# RCMX_Rev_00.net
KiCad netlist of a schematic drawn in EAGLE
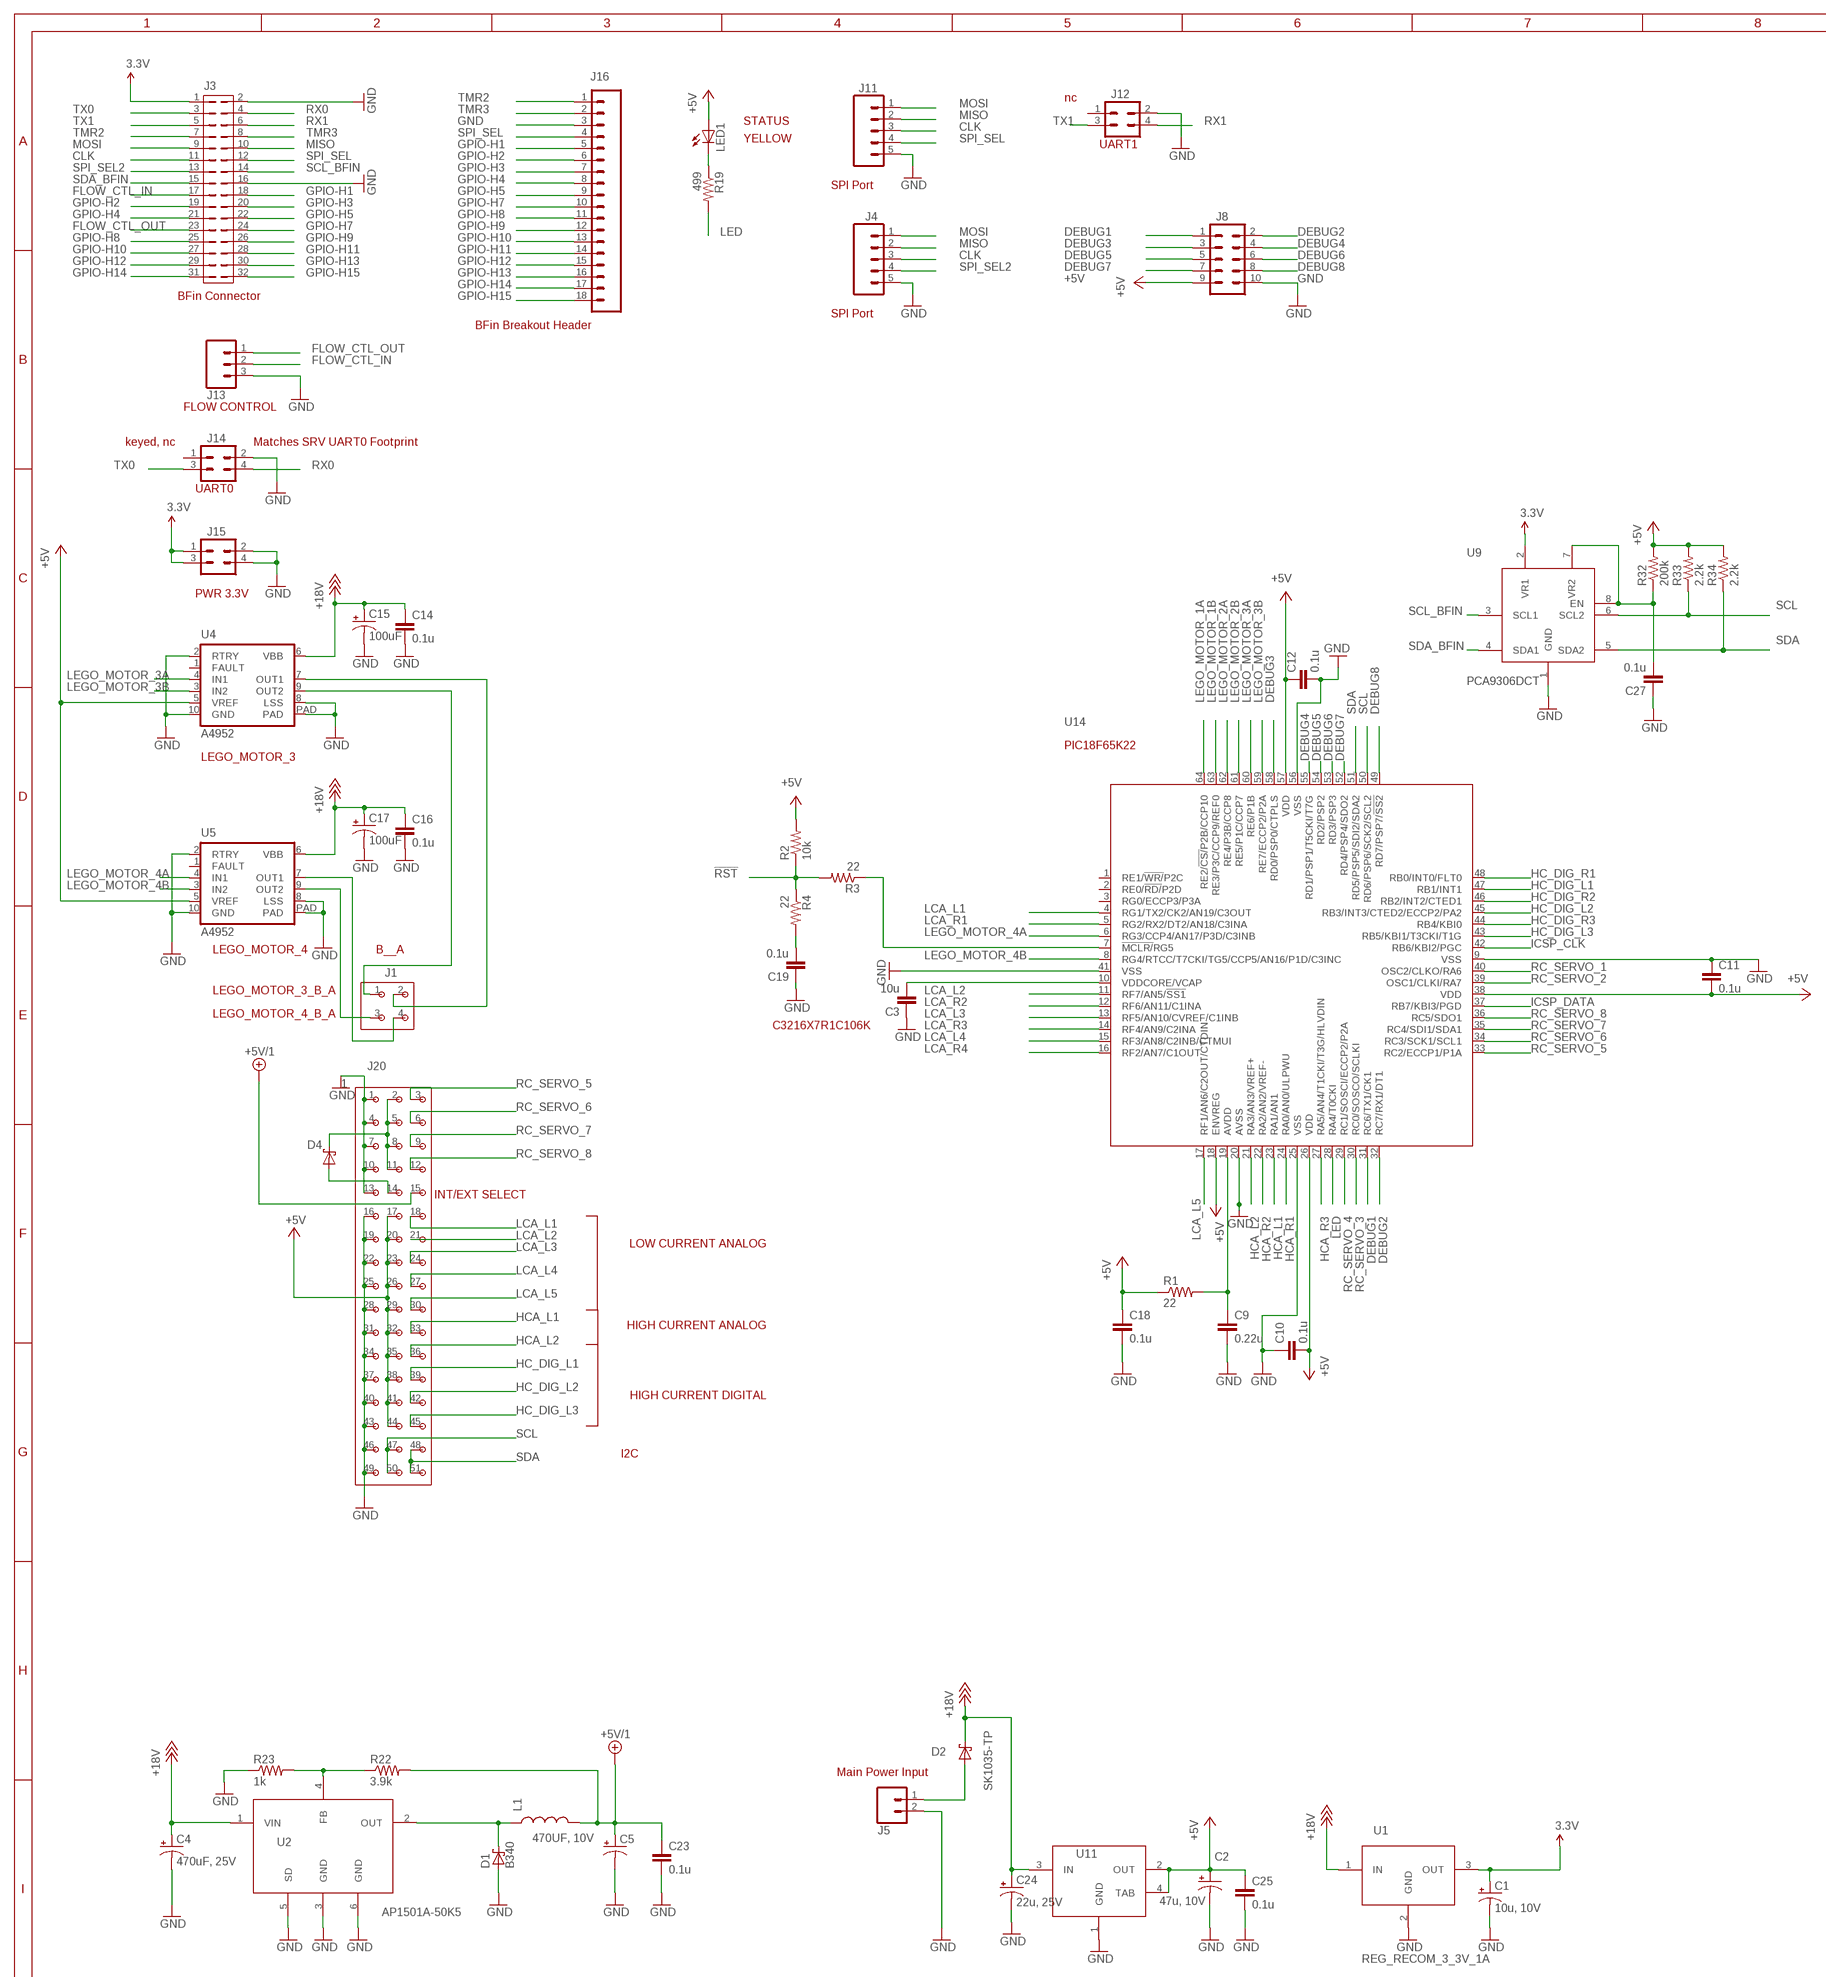
[diagram p0: schematic, sheet 1, part 1 of 2]
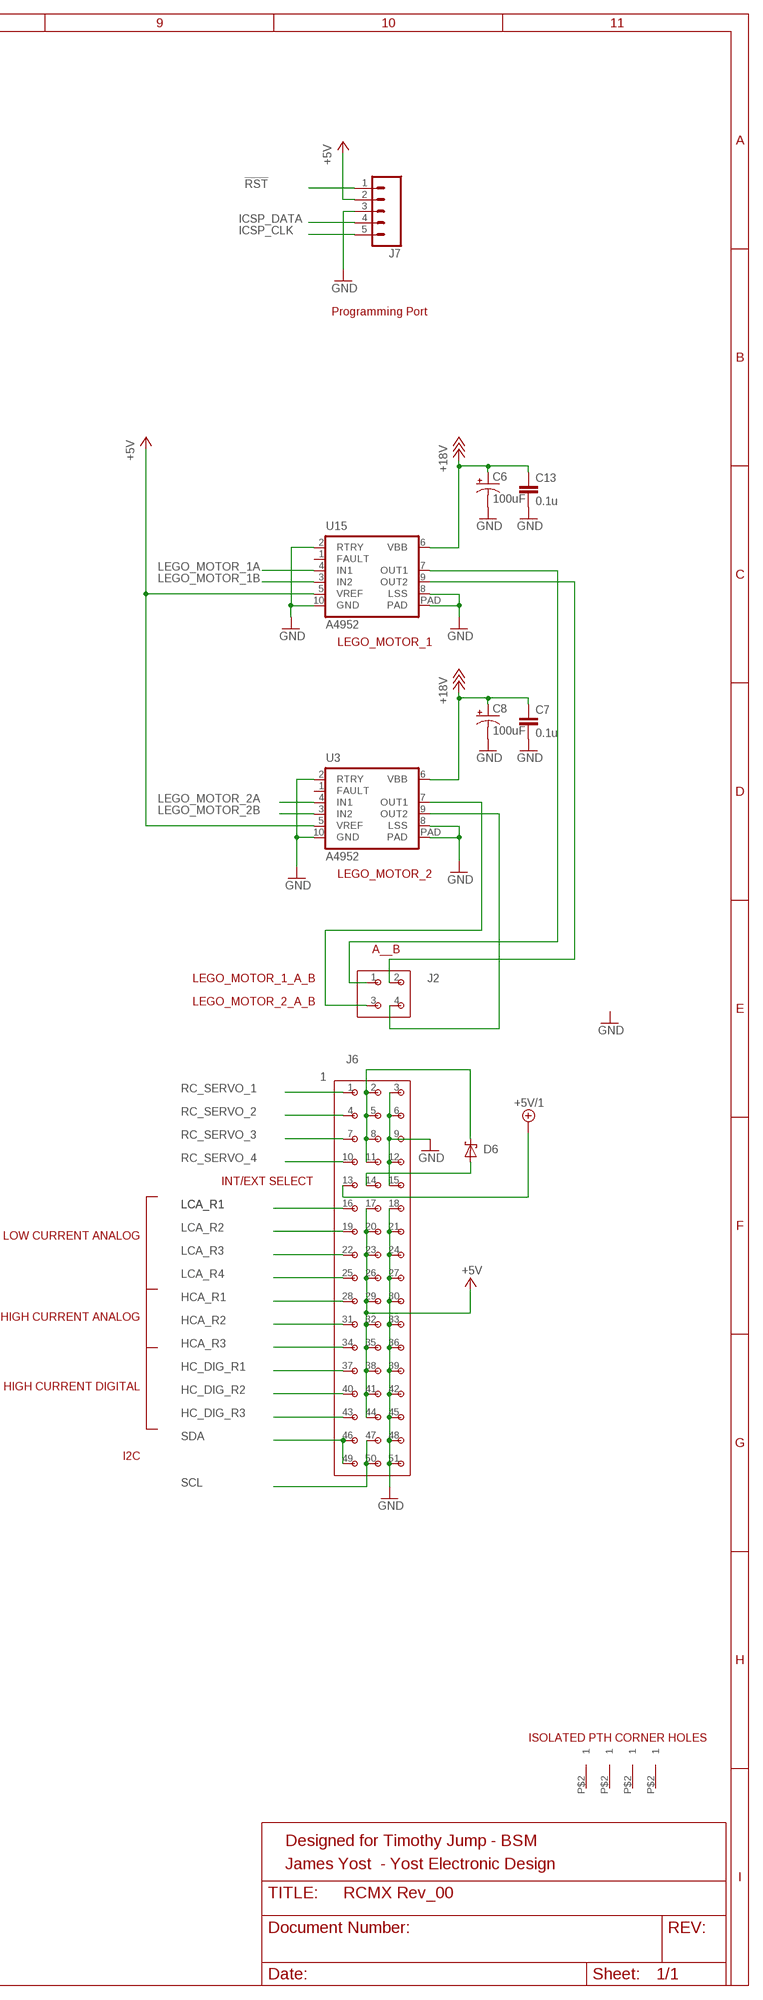
[diagram p1: schematic, sheet 1, part 2 of 2]

(export (version "E")
  (design (tool "Eeschema 10.0.6"))
  (components
    (comp (ref "C1")
      (value "10u, 10V")
      (footprint "eagle-import:EIA3216")
      (libsource (lib "eagle-import") (part "CAP_POL1206"))
    )
    (comp (ref "C2")
      (value "47u, 10V")
      (footprint "eagle-import:CAP1210_POL")
      (libsource (lib "eagle-import") (part "CAP_1210_POL"))
    )
    (comp (ref "C3")
      (value "10u")
      (footprint "eagle-import:1206")
      (libsource (lib "eagle-import") (part "CAP1206"))
    )
    (comp (ref "C4")
      (value "470uF, 25V")
      (footprint "eagle-import:PANASONIC_G")
      (libsource (lib "eagle-import") (part "CAP_POLG"))
    )
    (comp (ref "C5")
      (value "470UF, 10V")
      (footprint "eagle-import:PANASONIC_F")
      (libsource (lib "eagle-import") (part "CAP_ELT_PANASONIC_470UF"))
    )
    (comp (ref "C6")
      (value "100uF")
      (footprint "eagle-import:PANASONIC_D")
      (libsource (lib "eagle-import") (part "CAP_POLD"))
    )
    (comp (ref "C7")
      (value "0.1u")
      (footprint "eagle-import:0805")
      (libsource (lib "eagle-import") (part "CAP0805"))
    )
    (comp (ref "C8")
      (value "100uF")
      (footprint "eagle-import:PANASONIC_D")
      (libsource (lib "eagle-import") (part "CAP_POLD"))
    )
    (comp (ref "C9")
      (value "0.22u")
      (footprint "eagle-import:0805")
      (libsource (lib "eagle-import") (part "CAP0805"))
    )
    (comp (ref "C10")
      (value "0.1u")
      (footprint "eagle-import:0805")
      (libsource (lib "eagle-import") (part "CAP0805"))
    )
    (comp (ref "C11")
      (value "0.1u")
      (footprint "eagle-import:0805")
      (libsource (lib "eagle-import") (part "CAP0805"))
    )
    (comp (ref "C12")
      (value "0.1u")
      (footprint "eagle-import:0805")
      (libsource (lib "eagle-import") (part "CAP0805"))
    )
    (comp (ref "C13")
      (value "0.1u")
      (footprint "eagle-import:0805")
      (libsource (lib "eagle-import") (part "CAP0805"))
    )
    (comp (ref "C14")
      (value "0.1u")
      (footprint "eagle-import:0805")
      (libsource (lib "eagle-import") (part "CAP0805"))
    )
    (comp (ref "C15")
      (value "100uF")
      (footprint "eagle-import:PANASONIC_D")
      (libsource (lib "eagle-import") (part "CAP_POLD"))
    )
    (comp (ref "C16")
      (value "0.1u")
      (footprint "eagle-import:0805")
      (libsource (lib "eagle-import") (part "CAP0805"))
    )
    (comp (ref "C17")
      (value "100uF")
      (footprint "eagle-import:PANASONIC_D")
      (libsource (lib "eagle-import") (part "CAP_POLD"))
    )
    (comp (ref "C18")
      (value "0.1u")
      (footprint "eagle-import:0805")
      (libsource (lib "eagle-import") (part "CAP0805"))
    )
    (comp (ref "C19")
      (value "0.1u")
      (footprint "eagle-import:0805")
      (libsource (lib "eagle-import") (part "CAP0805"))
    )
    (comp (ref "C23")
      (value "0.1u")
      (footprint "eagle-import:0805")
      (libsource (lib "eagle-import") (part "CAP0805"))
    )
    (comp (ref "C24")
      (value "22u, 25V")
      (footprint "eagle-import:CAP1210_POL")
      (libsource (lib "eagle-import") (part "CAP_1210_POL"))
    )
    (comp (ref "C25")
      (value "0.1u")
      (footprint "eagle-import:0805")
      (libsource (lib "eagle-import") (part "CAP0805"))
    )
    (comp (ref "C27")
      (value "0.1u")
      (footprint "eagle-import:0805")
      (libsource (lib "eagle-import") (part "CAP0805"))
    )
    (comp (ref "D1")
      (value "B340")
      (footprint "eagle-import:SMA_DO214AC")
      (libsource (lib "eagle-import") (part "B340"))
    )
    (comp (ref "D2")
      (value "SK1035-TP")
      (footprint "eagle-import:DO214AB")
      (libsource (lib "eagle-import") (part "SK1035-TP"))
    )
    (comp (ref "D4")
      (value "SK1035-TP")
      (footprint "eagle-import:DO214AB")
      (libsource (lib "eagle-import") (part "SK1035-TP"))
    )
    (comp (ref "D6")
      (value "SK1035-TP")
      (footprint "eagle-import:DO214AB")
      (libsource (lib "eagle-import") (part "SK1035-TP"))
    )
    (comp (ref "J1")
      (value "CON_2X2_0_100")
      (footprint "eagle-import:CON_2X2_0_100")
      (libsource (lib "eagle-import") (part "CON_2X2_0_100"))
    )
    (comp (ref "J2")
      (value "CON_2X2_0_100")
      (footprint "eagle-import:CON_2X2_0_100")
      (libsource (lib "eagle-import") (part "CON_2X2_0_100"))
    )
    (comp (ref "J3")
      (value "CON_2X16_0_100")
      (footprint "eagle-import:CON_2X16_0_100")
      (libsource (lib "eagle-import") (part "CON_2X16_0_100"))
    )
    (comp (ref "J4")
      (value "M05PTH")
      (footprint "eagle-import:1X05")
      (libsource (lib "eagle-import") (part "M05PTH"))
    )
    (comp (ref "J5")
      (value "M02NG")
      (footprint "eagle-import:1X02")
      (libsource (lib "eagle-import") (part "M02NG"))
    )
    (comp (ref "J6")
      (value "CON_3X17_0_100")
      (footprint "eagle-import:CON_3X17_0_100")
      (libsource (lib "eagle-import") (part "CON_3X17_0_100"))
    )
    (comp (ref "J7")
      (value "M05PTH")
      (footprint "eagle-import:1X05")
      (libsource (lib "eagle-import") (part "SparkFun-Connectors_M05PTH"))
    )
    (comp (ref "J8")
      (value "M05X2PTH")
      (footprint "eagle-import:AVR_ICSP")
      (libsource (lib "eagle-import") (part "M05X2PTH"))
    )
    (comp (ref "J11")
      (value "M05PTH")
      (footprint "eagle-import:1X05")
      (libsource (lib "eagle-import") (part "M05PTH"))
    )
    (comp (ref "J12")
      (value "CON2X2")
      (footprint "eagle-import:CON2X2")
      (libsource (lib "eagle-import") (part "CON2X2"))
    )
    (comp (ref "J13")
      (value "M03PTH")
      (footprint "eagle-import:1X03")
      (libsource (lib "eagle-import") (part "M03PTH"))
    )
    (comp (ref "J14")
      (value "CON2X2")
      (footprint "eagle-import:CON2X2")
      (libsource (lib "eagle-import") (part "CON2X2"))
    )
    (comp (ref "J15")
      (value "CON2X2")
      (footprint "eagle-import:CON2X2")
      (libsource (lib "eagle-import") (part "CON2X2"))
    )
    (comp (ref "J16")
      (value "CON1X18")
      (footprint "eagle-import:CON1X18")
      (libsource (lib "eagle-import") (part "CON1X18"))
    )
    (comp (ref "J20")
      (value "CON_3X17_0_100")
      (footprint "eagle-import:CON_3X17_0_100")
      (libsource (lib "eagle-import") (part "CON_3X17_0_100"))
    )
    (comp (ref "L1")
      (value "IND_47UH_COILTRONICS_2_95A")
      (footprint "eagle-import:IND_PADS_SMT")
      (libsource (lib "eagle-import") (part "IND_47UH_COILTRONICS_2_95A"))
    )
    (comp (ref "LED1")
      (value "LEDCHIP-LED0805")
      (footprint "eagle-import:CHIP-LED0805")
      (libsource (lib "eagle-import") (part "LEDCHIP-LED0805"))
    )
    (comp (ref "R1")
      (value "22")
      (footprint "eagle-import:0805")
      (libsource (lib "eagle-import") (part "RESISTOR"))
    )
    (comp (ref "R2")
      (value "10k")
      (footprint "eagle-import:0805")
      (libsource (lib "eagle-import") (part "RESISTOR"))
    )
    (comp (ref "R3")
      (value "22")
      (footprint "eagle-import:0805")
      (libsource (lib "eagle-import") (part "RESISTOR"))
    )
    (comp (ref "R4")
      (value "22")
      (footprint "eagle-import:0805")
      (libsource (lib "eagle-import") (part "RESISTOR"))
    )
    (comp (ref "R19")
      (value "499")
      (footprint "eagle-import:0805")
      (libsource (lib "eagle-import") (part "RESISTOR"))
    )
    (comp (ref "R22")
      (value "3.9k")
      (footprint "eagle-import:0805")
      (libsource (lib "eagle-import") (part "RESISTOR"))
    )
    (comp (ref "R23")
      (value "1k")
      (footprint "eagle-import:0805")
      (libsource (lib "eagle-import") (part "RESISTOR"))
    )
    (comp (ref "R32")
      (value "200k")
      (footprint "eagle-import:0805")
      (libsource (lib "eagle-import") (part "RESISTOR"))
    )
    (comp (ref "R33")
      (value "2.2k")
      (footprint "eagle-import:0805")
      (libsource (lib "eagle-import") (part "RESISTOR"))
    )
    (comp (ref "R34")
      (value "2.2k")
      (footprint "eagle-import:0805")
      (libsource (lib "eagle-import") (part "RESISTOR"))
    )
    (comp (ref "U$1")
      (value "GNDPAD")
      (footprint "eagle-import:GNDPAD")
      (libsource (lib "eagle-import") (part "GNDPAD"))
    )
    (comp (ref "U$2")
      (value "GNDPAD")
      (footprint "eagle-import:GNDPAD")
      (libsource (lib "eagle-import") (part "GNDPAD"))
    )
    (comp (ref "U$7")
      (value "GNDPAD")
      (footprint "eagle-import:GNDPAD")
      (libsource (lib "eagle-import") (part "GNDPAD"))
    )
    (comp (ref "U$8")
      (value "GNDPAD")
      (footprint "eagle-import:GNDPAD")
      (libsource (lib "eagle-import") (part "GNDPAD"))
    )
    (comp (ref "U1")
      (value "REG_RECOM_3_3V_1A")
      (footprint "eagle-import:REG_RECOM_3_3V_1A")
      (libsource (lib "eagle-import") (part "REG_RECOM_3_3V_1A"))
    )
    (comp (ref "U2")
      (value "AP1501A-50K5")
      (footprint "eagle-import:TO263-5")
      (libsource (lib "eagle-import") (part "AP1501A-50K5"))
    )
    (comp (ref "U3")
      (value "A4952")
      (footprint "eagle-import:MSOP10_W_THERMAL_PAD")
      (libsource (lib "eagle-import") (part "A4952"))
    )
    (comp (ref "U4")
      (value "A4952")
      (footprint "eagle-import:MSOP10_W_THERMAL_PAD")
      (libsource (lib "eagle-import") (part "A4952"))
    )
    (comp (ref "U5")
      (value "A4952")
      (footprint "eagle-import:MSOP10_W_THERMAL_PAD")
      (libsource (lib "eagle-import") (part "A4952"))
    )
    (comp (ref "U9")
      (value "PCA9306DCT")
      (footprint "eagle-import:TEST08")
      (libsource (lib "eagle-import") (part "PCA9306DCT"))
    )
    (comp (ref "U11")
      (value "TLV1117-5")
      (footprint "eagle-import:SOT223")
      (libsource (lib "eagle-import") (part "TLV1117-5"))
    )
    (comp (ref "U14")
      (value "MICRO_C_PIC18F65K22")
      (footprint "eagle-import:64PIN_TQFP_10X10X1MM")
      (libsource (lib "eagle-import") (part "MICRO_C_PIC18F65K22"))
    )
    (comp (ref "U15")
      (value "A4952")
      (footprint "eagle-import:MSOP10_W_THERMAL_PAD")
      (libsource (lib "eagle-import") (part "A4952"))
    )
  )
  (nets
    (net (code "1") (name "+5V") (class "Default")
      (node (ref "C10") (pin "2") (pinfunction "2_2") (pintype "passive"))
      (node (ref "C11") (pin "2") (pinfunction "2_2") (pintype "passive"))
      (node (ref "C12") (pin "1") (pinfunction "1_1") (pintype "passive"))
      (node (ref "C18") (pin "1") (pinfunction "1_1") (pintype "passive"))
      (node (ref "C2") (pin "1") (pinfunction "+_1") (pintype "passive"))
      (node (ref "C25") (pin "1") (pinfunction "1_1") (pintype "passive"))
      (node (ref "J20") (pin "17") (pinfunction "17_17") (pintype "passive"))
      (node (ref "J20") (pin "20") (pinfunction "20_20") (pintype "passive"))
      (node (ref "J20") (pin "23") (pinfunction "23_23") (pintype "passive"))
      (node (ref "J20") (pin "26") (pinfunction "26_26") (pintype "passive"))
      (node (ref "J20") (pin "29") (pinfunction "29_29") (pintype "passive"))
      (node (ref "J20") (pin "32") (pinfunction "32_32") (pintype "passive"))
      (node (ref "J20") (pin "35") (pinfunction "35_35") (pintype "passive"))
      (node (ref "J20") (pin "38") (pinfunction "38_38") (pintype "passive"))
      (node (ref "J20") (pin "41") (pinfunction "41_41") (pintype "passive"))
      (node (ref "J20") (pin "44") (pinfunction "44_44") (pintype "passive"))
      (node (ref "J6") (pin "17") (pinfunction "17_17") (pintype "passive"))
      (node (ref "J6") (pin "20") (pinfunction "20_20") (pintype "passive"))
      (node (ref "J6") (pin "23") (pinfunction "23_23") (pintype "passive"))
      (node (ref "J6") (pin "26") (pinfunction "26_26") (pintype "passive"))
      (node (ref "J6") (pin "29") (pinfunction "29_29") (pintype "passive"))
      (node (ref "J6") (pin "32") (pinfunction "32_32") (pintype "passive"))
      (node (ref "J6") (pin "35") (pinfunction "35_35") (pintype "passive"))
      (node (ref "J6") (pin "38") (pinfunction "38_38") (pintype "passive"))
      (node (ref "J6") (pin "41") (pinfunction "41_41") (pintype "passive"))
      (node (ref "J6") (pin "44") (pinfunction "44_44") (pintype "passive"))
      (node (ref "J7") (pin "2") (pinfunction "2_2") (pintype "passive"))
      (node (ref "J8") (pin "9") (pinfunction "9_9") (pintype "passive"))
      (node (ref "LED1") (pin "A") (pinfunction "A_A") (pintype "passive"))
      (node (ref "R1") (pin "1") (pinfunction "1_1") (pintype "passive"))
      (node (ref "R2") (pin "2") (pinfunction "2_2") (pintype "passive"))
      (node (ref "R32") (pin "2") (pinfunction "2_2") (pintype "passive"))
      (node (ref "R33") (pin "2") (pinfunction "2_2") (pintype "passive"))
      (node (ref "R34") (pin "2") (pinfunction "2_2") (pintype "passive"))
      (node (ref "U11") (pin "2") (pinfunction "OUT_2") (pintype "bidirectional"))
      (node (ref "U11") (pin "4") (pinfunction "TAB_4") (pintype "bidirectional"))
      (node (ref "U14") (pin "18") (pinfunction "ENVREG_18") (pintype "input"))
      (node (ref "U14") (pin "26") (pinfunction "VDD_26") (pintype "power_in"))
      (node (ref "U14") (pin "38") (pinfunction "VDD_38") (pintype "power_in"))
      (node (ref "U14") (pin "57") (pinfunction "VDD_57") (pintype "power_in"))
      (node (ref "U15") (pin "5") (pinfunction "VREF_5") (pintype "passive"))
      (node (ref "U3") (pin "5") (pinfunction "VREF_5") (pintype "passive"))
      (node (ref "U4") (pin "5") (pinfunction "VREF_5") (pintype "passive"))
      (node (ref "U5") (pin "5") (pinfunction "VREF_5") (pintype "passive"))
    )
    (net (code "2") (name "+5V{slash}1") (class "Default")
      (node (ref "C23") (pin "1") (pinfunction "1_1") (pintype "passive"))
      (node (ref "C5") (pin "+") (pinfunction "+_+") (pintype "passive"))
      (node (ref "J20") (pin "15") (pinfunction "15_15") (pintype "passive"))
      (node (ref "J6") (pin "13") (pinfunction "13_13") (pintype "passive"))
      (node (ref "L1") (pin "2") (pinfunction "2_2") (pintype "passive"))
      (node (ref "R22") (pin "2") (pinfunction "2_2") (pintype "passive"))
    )
    (net (code "3") (name "+18V") (class "Default")
      (node (ref "C13") (pin "1") (pinfunction "1_1") (pintype "passive"))
      (node (ref "C14") (pin "1") (pinfunction "1_1") (pintype "passive"))
      (node (ref "C15") (pin "+") (pinfunction "+_+") (pintype "passive"))
      (node (ref "C16") (pin "1") (pinfunction "1_1") (pintype "passive"))
      (node (ref "C17") (pin "+") (pinfunction "+_+") (pintype "passive"))
      (node (ref "C24") (pin "1") (pinfunction "+_1") (pintype "passive"))
      (node (ref "C4") (pin "+") (pinfunction "+_+") (pintype "passive"))
      (node (ref "C6") (pin "+") (pinfunction "+_+") (pintype "passive"))
      (node (ref "C7") (pin "1") (pinfunction "1_1") (pintype "passive"))
      (node (ref "C8") (pin "+") (pinfunction "+_+") (pintype "passive"))
      (node (ref "D2") (pin "1") (pinfunction "C_1") (pintype "passive"))
      (node (ref "U1") (pin "1") (pinfunction "IN_1") (pintype "bidirectional"))
      (node (ref "U11") (pin "3") (pinfunction "IN_3") (pintype "bidirectional"))
      (node (ref "U15") (pin "6") (pinfunction "VBB_6") (pintype "input"))
      (node (ref "U2") (pin "1") (pinfunction "VIN_1") (pintype "bidirectional"))
      (node (ref "U3") (pin "6") (pinfunction "VBB_6") (pintype "input"))
      (node (ref "U4") (pin "6") (pinfunction "VBB_6") (pintype "input"))
      (node (ref "U5") (pin "6") (pinfunction "VBB_6") (pintype "input"))
    )
    (net (code "4") (name "/CLK") (class "Default")
      (node (ref "J11") (pin "3") (pinfunction "3_3") (pintype "passive"))
      (node (ref "J3") (pin "11") (pinfunction "11_11") (pintype "passive"))
      (node (ref "J4") (pin "3") (pinfunction "3_3") (pintype "passive"))
    )
    (net (code "5") (name "/DEBUG1") (class "Default")
      (node (ref "J8") (pin "1") (pinfunction "1_1") (pintype "passive"))
      (node (ref "U14") (pin "31") (pinfunction "RC6/TX1/CK1_31") (pintype "bidirectional"))
    )
    (net (code "6") (name "/DEBUG2") (class "Default")
      (node (ref "J8") (pin "2") (pinfunction "2_2") (pintype "passive"))
      (node (ref "U14") (pin "32") (pinfunction "RC7/RX1/DT1_32") (pintype "bidirectional"))
    )
    (net (code "7") (name "/DEBUG3") (class "Default")
      (node (ref "J8") (pin "3") (pinfunction "3_3") (pintype "passive"))
      (node (ref "U14") (pin "58") (pinfunction "RD0/PSP0/CTPLS_58") (pintype "bidirectional"))
    )
    (net (code "8") (name "/DEBUG4") (class "Default")
      (node (ref "J8") (pin "4") (pinfunction "4_4") (pintype "passive"))
      (node (ref "U14") (pin "55") (pinfunction "RD1/PSP1/T5CKI/T7G_55") (pintype "bidirectional"))
    )
    (net (code "9") (name "/DEBUG5") (class "Default")
      (node (ref "J8") (pin "5") (pinfunction "5_5") (pintype "passive"))
      (node (ref "U14") (pin "54") (pinfunction "RD2/PSP2_54") (pintype "bidirectional"))
    )
    (net (code "10") (name "/DEBUG6") (class "Default")
      (node (ref "J8") (pin "6") (pinfunction "6_6") (pintype "passive"))
      (node (ref "U14") (pin "53") (pinfunction "RD3/PSP3_53") (pintype "bidirectional"))
    )
    (net (code "11") (name "/DEBUG7") (class "Default")
      (node (ref "J8") (pin "7") (pinfunction "7_7") (pintype "passive"))
      (node (ref "U14") (pin "52") (pinfunction "RD4/PSP4/SDO2_52") (pintype "bidirectional"))
    )
    (net (code "12") (name "/DEBUG8") (class "Default")
      (node (ref "J8") (pin "8") (pinfunction "8_8") (pintype "passive"))
      (node (ref "U14") (pin "49") (pinfunction "RD7/PSP7/~{SS2}_49") (pintype "bidirectional"))
    )
    (net (code "13") (name "/FLOW_CTL_IN") (class "Default")
      (node (ref "J13") (pin "2") (pinfunction "2_2") (pintype "passive"))
      (node (ref "J3") (pin "17") (pinfunction "17_17") (pintype "passive"))
    )
    (net (code "14") (name "/FLOW_CTL_OUT") (class "Default")
      (node (ref "J13") (pin "1") (pinfunction "1_1") (pintype "passive"))
      (node (ref "J3") (pin "23") (pinfunction "23_23") (pintype "passive"))
    )
    (net (code "15") (name "/GPIO-H1") (class "Default")
      (node (ref "J16") (pin "5") (pinfunction "5_5") (pintype "passive"))
      (node (ref "J3") (pin "18") (pinfunction "18_18") (pintype "passive"))
    )
    (net (code "16") (name "/GPIO-H2") (class "Default")
      (node (ref "J16") (pin "6") (pinfunction "6_6") (pintype "passive"))
      (node (ref "J3") (pin "19") (pinfunction "19_19") (pintype "passive"))
    )
    (net (code "17") (name "/GPIO-H3") (class "Default")
      (node (ref "J16") (pin "7") (pinfunction "7_7") (pintype "passive"))
      (node (ref "J3") (pin "20") (pinfunction "20_20") (pintype "passive"))
    )
    (net (code "18") (name "/GPIO-H4") (class "Default")
      (node (ref "J16") (pin "8") (pinfunction "8_8") (pintype "passive"))
      (node (ref "J3") (pin "21") (pinfunction "21_21") (pintype "passive"))
    )
    (net (code "19") (name "/GPIO-H5") (class "Default")
      (node (ref "J16") (pin "9") (pinfunction "9_9") (pintype "passive"))
      (node (ref "J3") (pin "22") (pinfunction "22_22") (pintype "passive"))
    )
    (net (code "20") (name "/GPIO-H7") (class "Default")
      (node (ref "J16") (pin "10") (pinfunction "10_10") (pintype "passive"))
      (node (ref "J3") (pin "24") (pinfunction "24_24") (pintype "passive"))
    )
    (net (code "21") (name "/GPIO-H8") (class "Default")
      (node (ref "J16") (pin "11") (pinfunction "11_11") (pintype "passive"))
      (node (ref "J3") (pin "25") (pinfunction "25_25") (pintype "passive"))
    )
    (net (code "22") (name "/GPIO-H9") (class "Default")
      (node (ref "J16") (pin "12") (pinfunction "12_12") (pintype "passive"))
      (node (ref "J3") (pin "26") (pinfunction "26_26") (pintype "passive"))
    )
    (net (code "23") (name "/GPIO-H10") (class "Default")
      (node (ref "J16") (pin "13") (pinfunction "13_13") (pintype "passive"))
      (node (ref "J3") (pin "27") (pinfunction "27_27") (pintype "passive"))
    )
    (net (code "24") (name "/GPIO-H11") (class "Default")
      (node (ref "J16") (pin "14") (pinfunction "14_14") (pintype "passive"))
      (node (ref "J3") (pin "28") (pinfunction "28_28") (pintype "passive"))
    )
    (net (code "25") (name "/GPIO-H12") (class "Default")
      (node (ref "J16") (pin "15") (pinfunction "15_15") (pintype "passive"))
      (node (ref "J3") (pin "29") (pinfunction "29_29") (pintype "passive"))
    )
    (net (code "26") (name "/GPIO-H13") (class "Default")
      (node (ref "J16") (pin "16") (pinfunction "16_16") (pintype "passive"))
      (node (ref "J3") (pin "30") (pinfunction "30_30") (pintype "passive"))
    )
    (net (code "27") (name "/GPIO-H14") (class "Default")
      (node (ref "J16") (pin "17") (pinfunction "17_17") (pintype "passive"))
      (node (ref "J3") (pin "31") (pinfunction "31_31") (pintype "passive"))
    )
    (net (code "28") (name "/GPIO-H15") (class "Default")
      (node (ref "J16") (pin "18") (pinfunction "18_18") (pintype "passive"))
      (node (ref "J3") (pin "32") (pinfunction "32_32") (pintype "passive"))
    )
    (net (code "29") (name "/HCA_L1") (class "Default")
      (node (ref "J20") (pin "33") (pinfunction "33_33") (pintype "passive"))
      (node (ref "U14") (pin "23") (pinfunction "RA1/AN1_23") (pintype "bidirectional"))
    )
    (net (code "30") (name "/HCA_L2") (class "Default")
      (node (ref "J20") (pin "36") (pinfunction "36_36") (pintype "passive"))
      (node (ref "U14") (pin "21") (pinfunction "RA3/AN3/VREF+_21") (pintype "bidirectional"))
    )
    (net (code "31") (name "/HCA_R1") (class "Default")
      (node (ref "J6") (pin "28") (pinfunction "28_28") (pintype "passive"))
      (node (ref "U14") (pin "24") (pinfunction "RA0/AN0/ULPWU_24") (pintype "bidirectional"))
    )
    (net (code "32") (name "/HCA_R2") (class "Default")
      (node (ref "J6") (pin "31") (pinfunction "31_31") (pintype "passive"))
      (node (ref "U14") (pin "22") (pinfunction "RA2/AN2/VREF-_22") (pintype "bidirectional"))
    )
    (net (code "33") (name "/HCA_R3") (class "Default")
      (node (ref "J6") (pin "34") (pinfunction "34_34") (pintype "passive"))
      (node (ref "U14") (pin "27") (pinfunction "RA5/AN4/T1CKI/T3G/HLVDIN_27") (pintype "bidirectional"))
    )
    (net (code "34") (name "/HC_DIG_L1") (class "Default")
      (node (ref "J20") (pin "39") (pinfunction "39_39") (pintype "passive"))
      (node (ref "U14") (pin "47") (pinfunction "RB1/INT1_47") (pintype "bidirectional"))
    )
    (net (code "35") (name "/HC_DIG_L2") (class "Default")
      (node (ref "J20") (pin "42") (pinfunction "42_42") (pintype "passive"))
      (node (ref "U14") (pin "45") (pinfunction "RB3/INT3/CTED2/ECCP2/PA2_45") (pintype "bidirectional"))
    )
    (net (code "36") (name "/HC_DIG_L3") (class "Default")
      (node (ref "J20") (pin "45") (pinfunction "45_45") (pintype "passive"))
      (node (ref "U14") (pin "43") (pinfunction "RB5/KBI1/T3CKI/T1G_43") (pintype "bidirectional"))
    )
    (net (code "37") (name "/HC_DIG_R1") (class "Default")
      (node (ref "J6") (pin "37") (pinfunction "37_37") (pintype "passive"))
      (node (ref "U14") (pin "48") (pinfunction "RB0/INT0/FLT0_48") (pintype "bidirectional"))
    )
    (net (code "38") (name "/HC_DIG_R2") (class "Default")
      (node (ref "J6") (pin "40") (pinfunction "40_40") (pintype "passive"))
      (node (ref "U14") (pin "46") (pinfunction "RB2/INT2/CTED1_46") (pintype "bidirectional"))
    )
    (net (code "39") (name "/HC_DIG_R3") (class "Default")
      (node (ref "J6") (pin "43") (pinfunction "43_43") (pintype "passive"))
      (node (ref "U14") (pin "44") (pinfunction "RB4/KBI0_44") (pintype "bidirectional"))
    )
    (net (code "40") (name "/ICSP_CLK") (class "Default")
      (node (ref "J7") (pin "5") (pinfunction "5_5") (pintype "passive"))
      (node (ref "U14") (pin "42") (pinfunction "RB6/KBI2/PGC_42") (pintype "bidirectional"))
    )
    (net (code "41") (name "/ICSP_DATA") (class "Default")
      (node (ref "J7") (pin "4") (pinfunction "4_4") (pintype "passive"))
      (node (ref "U14") (pin "37") (pinfunction "RB7/KBI3/PGD_37") (pintype "bidirectional"))
    )
    (net (code "42") (name "/LCA_L1") (class "Default")
      (node (ref "J20") (pin "18") (pinfunction "18_18") (pintype "passive"))
      (node (ref "U14") (pin "4") (pinfunction "RG1/TX2/CK2/AN19/C3OUT_4") (pintype "bidirectional"))
    )
    (net (code "43") (name "/LCA_L2") (class "Default")
      (node (ref "J20") (pin "21") (pinfunction "21_21") (pintype "passive"))
      (node (ref "U14") (pin "11") (pinfunction "RF7/AN5/~{SS1}_11") (pintype "bidirectional"))
    )
    (net (code "44") (name "/LCA_L3") (class "Default")
      (node (ref "J20") (pin "24") (pinfunction "24_24") (pintype "passive"))
      (node (ref "U14") (pin "13") (pinfunction "RF5/AN10/CVREF/C1INB_13") (pintype "bidirectional"))
    )
    (net (code "45") (name "/LCA_L4") (class "Default")
      (node (ref "J20") (pin "27") (pinfunction "27_27") (pintype "passive"))
      (node (ref "U14") (pin "15") (pinfunction "RF3/AN8/C2INB/CTMUI_15") (pintype "bidirectional"))
    )
    (net (code "46") (name "/LCA_L5") (class "Default")
      (node (ref "J20") (pin "30") (pinfunction "30_30") (pintype "passive"))
      (node (ref "U14") (pin "17") (pinfunction "RF1/AN6/C2OUT/CTDIN_17") (pintype "bidirectional"))
    )
    (net (code "47") (name "/LCA_R1") (class "Default")
      (node (ref "J6") (pin "16") (pinfunction "16_16") (pintype "passive"))
      (node (ref "U14") (pin "5") (pinfunction "RG2/RX2/DT2/AN18/C3INA_5") (pintype "bidirectional"))
    )
    (net (code "48") (name "/LCA_R2") (class "Default")
      (node (ref "J6") (pin "19") (pinfunction "19_19") (pintype "passive"))
      (node (ref "U14") (pin "12") (pinfunction "RF6/AN11/C1INA_12") (pintype "bidirectional"))
    )
    (net (code "49") (name "/LCA_R3") (class "Default")
      (node (ref "J6") (pin "22") (pinfunction "22_22") (pintype "passive"))
      (node (ref "U14") (pin "14") (pinfunction "RF4/AN9/C2INA_14") (pintype "bidirectional"))
    )
    (net (code "50") (name "/LCA_R4") (class "Default")
      (node (ref "J6") (pin "25") (pinfunction "25_25") (pintype "passive"))
      (node (ref "U14") (pin "16") (pinfunction "RF2/AN7/C1OUT_16") (pintype "bidirectional"))
    )
    (net (code "51") (name "/LED") (class "Default")
      (node (ref "R19") (pin "2") (pinfunction "2_2") (pintype "passive"))
      (node (ref "U14") (pin "28") (pinfunction "RA4/T0CKI_28") (pintype "bidirectional"))
    )
    (net (code "52") (name "/LEGO_MOTOR_1A") (class "Default")
      (node (ref "U14") (pin "64") (pinfunction "RE2/~{CS/}P2B/CCP10_64") (pintype "bidirectional"))
      (node (ref "U15") (pin "4") (pinfunction "IN1_4") (pintype "input"))
    )
    (net (code "53") (name "/LEGO_MOTOR_1B") (class "Default")
      (node (ref "U14") (pin "63") (pinfunction "RE3/P3C/CCP9/REF0_63") (pintype "bidirectional"))
      (node (ref "U15") (pin "3") (pinfunction "IN2_3") (pintype "input"))
    )
    (net (code "54") (name "/LEGO_MOTOR_2A") (class "Default")
      (node (ref "U14") (pin "62") (pinfunction "RE4/P3B/CCP8_62") (pintype "bidirectional"))
      (node (ref "U3") (pin "4") (pinfunction "IN1_4") (pintype "input"))
    )
    (net (code "55") (name "/LEGO_MOTOR_2B") (class "Default")
      (node (ref "U14") (pin "61") (pinfunction "RE5/P1C/CCP7_61") (pintype "bidirectional"))
      (node (ref "U3") (pin "3") (pinfunction "IN2_3") (pintype "input"))
    )
    (net (code "56") (name "/LEGO_MOTOR_3A") (class "Default")
      (node (ref "U14") (pin "60") (pinfunction "RE6/P1B_60") (pintype "bidirectional"))
      (node (ref "U4") (pin "4") (pinfunction "IN1_4") (pintype "input"))
    )
    (net (code "57") (name "/LEGO_MOTOR_3B") (class "Default")
      (node (ref "U14") (pin "59") (pinfunction "RE7/ECCP2/P2A_59") (pintype "bidirectional"))
      (node (ref "U4") (pin "3") (pinfunction "IN2_3") (pintype "input"))
    )
    (net (code "58") (name "/LEGO_MOTOR_4A") (class "Default")
      (node (ref "U14") (pin "6") (pinfunction "RG3/CCP4/AN17/P3D/C3INB_6") (pintype "bidirectional"))
      (node (ref "U5") (pin "4") (pinfunction "IN1_4") (pintype "input"))
    )
    (net (code "59") (name "/LEGO_MOTOR_4B") (class "Default")
      (node (ref "U14") (pin "8") (pinfunction "RG4/RTCC/T7CKI/TG5/CCP5/AN16/P1D/C3INC_8") (pintype "bidirectional"))
      (node (ref "U5") (pin "3") (pinfunction "IN2_3") (pintype "input"))
    )
    (net (code "60") (name "/MISO") (class "Default")
      (node (ref "J11") (pin "2") (pinfunction "2_2") (pintype "passive"))
      (node (ref "J3") (pin "10") (pinfunction "10_10") (pintype "passive"))
      (node (ref "J4") (pin "2") (pinfunction "2_2") (pintype "passive"))
    )
    (net (code "61") (name "/MOSI") (class "Default")
      (node (ref "J11") (pin "1") (pinfunction "1_1") (pintype "passive"))
      (node (ref "J3") (pin "9") (pinfunction "9_9") (pintype "passive"))
      (node (ref "J4") (pin "1") (pinfunction "1_1") (pintype "passive"))
    )
    (net (code "62") (name "/RC_SERVO_1") (class "Default")
      (node (ref "J6") (pin "1") (pinfunction "1_1") (pintype "passive"))
      (node (ref "U14") (pin "40") (pinfunction "OSC2/CLKO/RA6_40") (pintype "output"))
    )
    (net (code "63") (name "/RC_SERVO_2") (class "Default")
      (node (ref "J6") (pin "4") (pinfunction "4_4") (pintype "passive"))
      (node (ref "U14") (pin "39") (pinfunction "OSC1/CLKI/RA7_39") (pintype "input"))
    )
    (net (code "64") (name "/RC_SERVO_3") (class "Default")
      (node (ref "J6") (pin "7") (pinfunction "7_7") (pintype "passive"))
      (node (ref "U14") (pin "30") (pinfunction "RC0/SOSCO/SCLKI_30") (pintype "bidirectional"))
    )
    (net (code "65") (name "/RC_SERVO_4") (class "Default")
      (node (ref "J6") (pin "10") (pinfunction "10_10") (pintype "passive"))
      (node (ref "U14") (pin "29") (pinfunction "RC1/SOSCI/ECCP2/P2A_29") (pintype "bidirectional"))
    )
    (net (code "66") (name "/RC_SERVO_5") (class "Default")
      (node (ref "J20") (pin "3") (pinfunction "3_3") (pintype "passive"))
      (node (ref "U14") (pin "33") (pinfunction "RC2/ECCP1/P1A_33") (pintype "bidirectional"))
    )
    (net (code "67") (name "/RC_SERVO_6") (class "Default")
      (node (ref "J20") (pin "6") (pinfunction "6_6") (pintype "passive"))
      (node (ref "U14") (pin "34") (pinfunction "RC3/SCK1/SCL1_34") (pintype "bidirectional"))
    )
    (net (code "68") (name "/RC_SERVO_7") (class "Default")
      (node (ref "J20") (pin "9") (pinfunction "9_9") (pintype "passive"))
      (node (ref "U14") (pin "35") (pinfunction "RC4/SDI1/SDA1_35") (pintype "bidirectional"))
    )
    (net (code "69") (name "/RC_SERVO_8") (class "Default")
      (node (ref "J20") (pin "12") (pinfunction "12_12") (pintype "passive"))
      (node (ref "U14") (pin "36") (pinfunction "RC5/SDO1_36") (pintype "bidirectional"))
    )
    (net (code "70") (name "/RX0") (class "Default")
      (node (ref "J14") (pin "4") (pinfunction "4_4") (pintype "passive"))
      (node (ref "J3") (pin "4") (pinfunction "4_4") (pintype "passive"))
    )
    (net (code "71") (name "/RX1") (class "Default")
      (node (ref "J12") (pin "4") (pinfunction "4_4") (pintype "passive"))
      (node (ref "J3") (pin "6") (pinfunction "6_6") (pintype "passive"))
    )
    (net (code "72") (name "/SCL") (class "Default")
      (node (ref "J20") (pin "47") (pinfunction "47_47") (pintype "passive"))
      (node (ref "J20") (pin "50") (pinfunction "50_50") (pintype "passive"))
      (node (ref "J6") (pin "47") (pinfunction "47_47") (pintype "passive"))
      (node (ref "J6") (pin "50") (pinfunction "50_50") (pintype "passive"))
      (node (ref "R33") (pin "1") (pinfunction "1_1") (pintype "passive"))
      (node (ref "U14") (pin "50") (pinfunction "RD6/PSP6/SCK2/SCL2_50") (pintype "bidirectional"))
      (node (ref "U9") (pin "6") (pinfunction "SCL2_6") (pintype "bidirectional"))
    )
    (net (code "73") (name "/SCL_BFIN") (class "Default")
      (node (ref "J3") (pin "14") (pinfunction "14_14") (pintype "passive"))
      (node (ref "U9") (pin "3") (pinfunction "SCL1_3") (pintype "bidirectional"))
    )
    (net (code "74") (name "/SDA") (class "Default")
      (node (ref "J20") (pin "48") (pinfunction "48_48") (pintype "passive"))
      (node (ref "J20") (pin "51") (pinfunction "51_51") (pintype "passive"))
      (node (ref "J6") (pin "46") (pinfunction "46_46") (pintype "passive"))
      (node (ref "J6") (pin "49") (pinfunction "49_49") (pintype "passive"))
      (node (ref "R34") (pin "1") (pinfunction "1_1") (pintype "passive"))
      (node (ref "U14") (pin "51") (pinfunction "RD5/PSP5/SDI2/SDA2_51") (pintype "bidirectional"))
      (node (ref "U9") (pin "5") (pinfunction "SDA2_5") (pintype "bidirectional"))
    )
    (net (code "75") (name "/SDA_BFIN") (class "Default")
      (node (ref "J3") (pin "15") (pinfunction "15_15") (pintype "passive"))
      (node (ref "U9") (pin "4") (pinfunction "SDA1_4") (pintype "bidirectional"))
    )
    (net (code "76") (name "/SPI_SEL") (class "Default")
      (node (ref "J11") (pin "4") (pinfunction "4_4") (pintype "passive"))
      (node (ref "J16") (pin "4") (pinfunction "4_4") (pintype "passive"))
      (node (ref "J3") (pin "12") (pinfunction "12_12") (pintype "passive"))
    )
    (net (code "77") (name "/SPI_SEL2") (class "Default")
      (node (ref "J3") (pin "13") (pinfunction "13_13") (pintype "passive"))
      (node (ref "J4") (pin "4") (pinfunction "4_4") (pintype "passive"))
    )
    (net (code "78") (name "/TMR2") (class "Default")
      (node (ref "J16") (pin "1") (pinfunction "1_1") (pintype "passive"))
      (node (ref "J3") (pin "7") (pinfunction "7_7") (pintype "passive"))
    )
    (net (code "79") (name "/TMR3") (class "Default")
      (node (ref "J16") (pin "2") (pinfunction "2_2") (pintype "passive"))
      (node (ref "J3") (pin "8") (pinfunction "8_8") (pintype "passive"))
    )
    (net (code "80") (name "/TX0") (class "Default")
      (node (ref "J14") (pin "3") (pinfunction "3_3") (pintype "passive"))
      (node (ref "J3") (pin "3") (pinfunction "3_3") (pintype "passive"))
    )
    (net (code "81") (name "/TX1") (class "Default")
      (node (ref "J12") (pin "3") (pinfunction "3_3") (pintype "passive"))
      (node (ref "J3") (pin "5") (pinfunction "5_5") (pintype "passive"))
    )
    (net (code "82") (name "/~{RST}") (class "Default")
      (node (ref "J7") (pin "1") (pinfunction "1_1") (pintype "passive"))
      (node (ref "R2") (pin "1") (pinfunction "1_1") (pintype "passive"))
      (node (ref "R3") (pin "2") (pinfunction "2_2") (pintype "passive"))
      (node (ref "R4") (pin "1") (pinfunction "1_1") (pintype "passive"))
    )
    (net (code "83") (name "3.3V") (class "Default")
      (node (ref "C1") (pin "A") (pinfunction "+_A") (pintype "passive"))
      (node (ref "J15") (pin "1") (pinfunction "1_1") (pintype "passive"))
      (node (ref "J15") (pin "3") (pinfunction "3_3") (pintype "passive"))
      (node (ref "J3") (pin "1") (pinfunction "1_1") (pintype "passive"))
      (node (ref "U1") (pin "3") (pinfunction "OUT_3") (pintype "bidirectional"))
      (node (ref "U9") (pin "2") (pinfunction "VR1_2") (pintype "bidirectional"))
    )
    (net (code "84") (name "GND") (class "Default")
      (node (ref "C1") (pin "C") (pinfunction "-_C") (pintype "passive"))
      (node (ref "C10") (pin "1") (pinfunction "1_1") (pintype "passive"))
      (node (ref "C11") (pin "1") (pinfunction "1_1") (pintype "passive"))
      (node (ref "C12") (pin "2") (pinfunction "2_2") (pintype "passive"))
      (node (ref "C13") (pin "2") (pinfunction "2_2") (pintype "passive"))
      (node (ref "C14") (pin "2") (pinfunction "2_2") (pintype "passive"))
      (node (ref "C15") (pin "-") (pinfunction "-_-") (pintype "passive"))
      (node (ref "C16") (pin "2") (pinfunction "2_2") (pintype "passive"))
      (node (ref "C17") (pin "-") (pinfunction "-_-") (pintype "passive"))
      (node (ref "C18") (pin "2") (pinfunction "2_2") (pintype "passive"))
      (node (ref "C19") (pin "1") (pinfunction "1_1") (pintype "passive"))
      (node (ref "C2") (pin "2") (pinfunction "-_2") (pintype "passive"))
      (node (ref "C23") (pin "2") (pinfunction "2_2") (pintype "passive"))
      (node (ref "C24") (pin "2") (pinfunction "-_2") (pintype "passive"))
      (node (ref "C25") (pin "2") (pinfunction "2_2") (pintype "passive"))
      (node (ref "C27") (pin "1") (pinfunction "1_1") (pintype "passive"))
      (node (ref "C3") (pin "1") (pinfunction "1_1") (pintype "passive"))
      (node (ref "C4") (pin "-") (pinfunction "-_-") (pintype "passive"))
      (node (ref "C5") (pin "-") (pinfunction "-_-") (pintype "passive"))
      (node (ref "C6") (pin "-") (pinfunction "-_-") (pintype "passive"))
      (node (ref "C7") (pin "2") (pinfunction "2_2") (pintype "passive"))
      (node (ref "C8") (pin "-") (pinfunction "-_-") (pintype "passive"))
      (node (ref "C9") (pin "2") (pinfunction "2_2") (pintype "passive"))
      (node (ref "D1") (pin "A") (pinfunction "A_A") (pintype "passive"))
      (node (ref "J11") (pin "5") (pinfunction "5_5") (pintype "passive"))
      (node (ref "J12") (pin "2") (pinfunction "2_2") (pintype "passive"))
      (node (ref "J13") (pin "3") (pinfunction "3_3") (pintype "passive"))
      (node (ref "J14") (pin "2") (pinfunction "2_2") (pintype "passive"))
      (node (ref "J15") (pin "2") (pinfunction "2_2") (pintype "passive"))
      (node (ref "J15") (pin "4") (pinfunction "4_4") (pintype "passive"))
      (node (ref "J16") (pin "3") (pinfunction "3_3") (pintype "passive"))
      (node (ref "J20") (pin "1") (pinfunction "1_1") (pintype "passive"))
      (node (ref "J20") (pin "10") (pinfunction "10_10") (pintype "passive"))
      (node (ref "J20") (pin "13") (pinfunction "13_13") (pintype "passive"))
      (node (ref "J20") (pin "16") (pinfunction "16_16") (pintype "passive"))
      (node (ref "J20") (pin "19") (pinfunction "19_19") (pintype "passive"))
      (node (ref "J20") (pin "22") (pinfunction "22_22") (pintype "passive"))
      (node (ref "J20") (pin "25") (pinfunction "25_25") (pintype "passive"))
      (node (ref "J20") (pin "28") (pinfunction "28_28") (pintype "passive"))
      (node (ref "J20") (pin "31") (pinfunction "31_31") (pintype "passive"))
      (node (ref "J20") (pin "34") (pinfunction "34_34") (pintype "passive"))
      (node (ref "J20") (pin "37") (pinfunction "37_37") (pintype "passive"))
      (node (ref "J20") (pin "4") (pinfunction "4_4") (pintype "passive"))
      (node (ref "J20") (pin "40") (pinfunction "40_40") (pintype "passive"))
      (node (ref "J20") (pin "43") (pinfunction "43_43") (pintype "passive"))
      (node (ref "J20") (pin "46") (pinfunction "46_46") (pintype "passive"))
      (node (ref "J20") (pin "49") (pinfunction "49_49") (pintype "passive"))
      (node (ref "J20") (pin "7") (pinfunction "7_7") (pintype "passive"))
      (node (ref "J3") (pin "16") (pinfunction "16_16") (pintype "passive"))
      (node (ref "J3") (pin "2") (pinfunction "2_2") (pintype "passive"))
      (node (ref "J4") (pin "5") (pinfunction "5_5") (pintype "passive"))
      (node (ref "J5") (pin "2") (pinfunction "2_2") (pintype "passive"))
      (node (ref "J6") (pin "12") (pinfunction "12_12") (pintype "passive"))
      (node (ref "J6") (pin "15") (pinfunction "15_15") (pintype "passive"))
      (node (ref "J6") (pin "18") (pinfunction "18_18") (pintype "passive"))
      (node (ref "J6") (pin "21") (pinfunction "21_21") (pintype "passive"))
      (node (ref "J6") (pin "24") (pinfunction "24_24") (pintype "passive"))
      (node (ref "J6") (pin "27") (pinfunction "27_27") (pintype "passive"))
      (node (ref "J6") (pin "3") (pinfunction "3_3") (pintype "passive"))
      (node (ref "J6") (pin "30") (pinfunction "30_30") (pintype "passive"))
      (node (ref "J6") (pin "33") (pinfunction "33_33") (pintype "passive"))
      (node (ref "J6") (pin "36") (pinfunction "36_36") (pintype "passive"))
      (node (ref "J6") (pin "39") (pinfunction "39_39") (pintype "passive"))
      (node (ref "J6") (pin "42") (pinfunction "42_42") (pintype "passive"))
      (node (ref "J6") (pin "45") (pinfunction "45_45") (pintype "passive"))
      (node (ref "J6") (pin "48") (pinfunction "48_48") (pintype "passive"))
      (node (ref "J6") (pin "51") (pinfunction "51_51") (pintype "passive"))
      (node (ref "J6") (pin "6") (pinfunction "6_6") (pintype "passive"))
      (node (ref "J6") (pin "9") (pinfunction "9_9") (pintype "passive"))
      (node (ref "J7") (pin "3") (pinfunction "3_3") (pintype "passive"))
      (node (ref "J8") (pin "10") (pinfunction "10_10") (pintype "passive"))
      (node (ref "R23") (pin "1") (pinfunction "1_1") (pintype "passive"))
      (node (ref "U1") (pin "2") (pinfunction "GND_2") (pintype "bidirectional"))
      (node (ref "U11") (pin "1") (pinfunction "GND_1") (pintype "bidirectional"))
      (node (ref "U14") (pin "20") (pinfunction "AVSS_20") (pintype "power_in"))
      (node (ref "U14") (pin "25") (pinfunction "VSS_25") (pintype "power_in"))
      (node (ref "U14") (pin "41") (pinfunction "VSS_41") (pintype "power_in"))
      (node (ref "U14") (pin "56") (pinfunction "VSS_56") (pintype "power_in"))
      (node (ref "U14") (pin "9") (pinfunction "VSS_9") (pintype "power_in"))
      (node (ref "U15") (pin "10") (pinfunction "GND_10") (pintype "power_in"))
      (node (ref "U15") (pin "2") (pinfunction "RTRY_2") (pintype "input"))
      (node (ref "U15") (pin "8") (pinfunction "LSS_8") (pintype "output"))
      (node (ref "U15") (pin "PAD") (pinfunction "PAD_PAD") (pintype "output"))
      (node (ref "U2") (pin "3") (pinfunction "GND_3") (pintype "bidirectional"))
      (node (ref "U2") (pin "5") (pinfunction "SD_5") (pintype "bidirectional"))
      (node (ref "U2") (pin "6") (pinfunction "GND_6") (pintype "bidirectional"))
      (node (ref "U3") (pin "10") (pinfunction "GND_10") (pintype "power_in"))
      (node (ref "U3") (pin "2") (pinfunction "RTRY_2") (pintype "input"))
      (node (ref "U3") (pin "8") (pinfunction "LSS_8") (pintype "output"))
      (node (ref "U3") (pin "PAD") (pinfunction "PAD_PAD") (pintype "output"))
      (node (ref "U4") (pin "10") (pinfunction "GND_10") (pintype "power_in"))
      (node (ref "U4") (pin "2") (pinfunction "RTRY_2") (pintype "input"))
      (node (ref "U4") (pin "8") (pinfunction "LSS_8") (pintype "output"))
      (node (ref "U4") (pin "PAD") (pinfunction "PAD_PAD") (pintype "output"))
      (node (ref "U5") (pin "10") (pinfunction "GND_10") (pintype "power_in"))
      (node (ref "U5") (pin "2") (pinfunction "RTRY_2") (pintype "input"))
      (node (ref "U5") (pin "8") (pinfunction "LSS_8") (pintype "output"))
      (node (ref "U5") (pin "PAD") (pinfunction "PAD_PAD") (pintype "output"))
      (node (ref "U9") (pin "1") (pinfunction "GND_1") (pintype "bidirectional"))
    )
    (net (code "85") (name "Net-(C19-Pad2)") (class "Default")
      (node (ref "C19") (pin "2") (pinfunction "2_2") (pintype "passive"))
      (node (ref "R4") (pin "2") (pinfunction "2_2") (pintype "passive"))
    )
    (net (code "86") (name "Net-(D2-A)") (class "Default")
      (node (ref "D2") (pin "2") (pinfunction "A_2") (pintype "passive"))
      (node (ref "J5") (pin "1") (pinfunction "1_1") (pintype "passive"))
    )
    (net (code "87") (name "Net-(D4-A)") (class "Default")
      (node (ref "D4") (pin "2") (pinfunction "A_2") (pintype "passive"))
      (node (ref "J20") (pin "14") (pinfunction "14_14") (pintype "passive"))
    )
    (net (code "88") (name "Net-(D4-C)") (class "Default")
      (node (ref "D4") (pin "1") (pinfunction "C_1") (pintype "passive"))
      (node (ref "J20") (pin "11") (pinfunction "11_11") (pintype "passive"))
      (node (ref "J20") (pin "2") (pinfunction "2_2") (pintype "passive"))
      (node (ref "J20") (pin "5") (pinfunction "5_5") (pintype "passive"))
      (node (ref "J20") (pin "8") (pinfunction "8_8") (pintype "passive"))
    )
    (net (code "89") (name "Net-(D6-A)") (class "Default")
      (node (ref "D6") (pin "2") (pinfunction "A_2") (pintype "passive"))
      (node (ref "J6") (pin "14") (pinfunction "14_14") (pintype "passive"))
    )
    (net (code "90") (name "Net-(D6-C)") (class "Default")
      (node (ref "D6") (pin "1") (pinfunction "C_1") (pintype "passive"))
      (node (ref "J6") (pin "11") (pinfunction "11_11") (pintype "passive"))
      (node (ref "J6") (pin "2") (pinfunction "2_2") (pintype "passive"))
      (node (ref "J6") (pin "5") (pinfunction "5_5") (pintype "passive"))
      (node (ref "J6") (pin "8") (pinfunction "8_8") (pintype "passive"))
    )
    (net (code "91") (name "Net-(LED1-PadC)") (class "Default")
      (node (ref "LED1") (pin "C") (pinfunction "C_C") (pintype "passive"))
      (node (ref "R19") (pin "1") (pinfunction "1_1") (pintype "passive"))
    )
    (net (code "92") (name "Net-(U2-FB)") (class "Default")
      (node (ref "R22") (pin "1") (pinfunction "1_1") (pintype "passive"))
      (node (ref "R23") (pin "2") (pinfunction "2_2") (pintype "passive"))
      (node (ref "U2") (pin "4") (pinfunction "FB_4") (pintype "bidirectional"))
    )
    (net (code "93") (name "Net-(U2-OUT)") (class "Default")
      (node (ref "D1") (pin "C") (pinfunction "C_C") (pintype "passive"))
      (node (ref "L1") (pin "1") (pinfunction "1_1") (pintype "passive"))
      (node (ref "U2") (pin "2") (pinfunction "OUT_2") (pintype "bidirectional"))
    )
    (net (code "94") (name "Net-(U3-OUT1)") (class "Default")
      (node (ref "J2") (pin "3") (pinfunction "3_3") (pintype "passive"))
      (node (ref "U3") (pin "7") (pinfunction "OUT1_7") (pintype "output"))
    )
    (net (code "95") (name "Net-(U3-OUT2)") (class "Default")
      (node (ref "J2") (pin "4") (pinfunction "4_4") (pintype "passive"))
      (node (ref "U3") (pin "9") (pinfunction "OUT2_9") (pintype "input"))
    )
    (net (code "96") (name "Net-(U4-OUT1)") (class "Default")
      (node (ref "J1") (pin "2") (pinfunction "2_2") (pintype "passive"))
      (node (ref "U4") (pin "7") (pinfunction "OUT1_7") (pintype "output"))
    )
    (net (code "97") (name "Net-(U4-OUT2)") (class "Default")
      (node (ref "J1") (pin "1") (pinfunction "1_1") (pintype "passive"))
      (node (ref "U4") (pin "9") (pinfunction "OUT2_9") (pintype "input"))
    )
    (net (code "98") (name "Net-(U5-OUT1)") (class "Default")
      (node (ref "J1") (pin "4") (pinfunction "4_4") (pintype "passive"))
      (node (ref "U5") (pin "7") (pinfunction "OUT1_7") (pintype "output"))
    )
    (net (code "99") (name "Net-(U5-OUT2)") (class "Default")
      (node (ref "J1") (pin "3") (pinfunction "3_3") (pintype "passive"))
      (node (ref "U5") (pin "9") (pinfunction "OUT2_9") (pintype "input"))
    )
    (net (code "100") (name "Net-(U9-EN)") (class "Default")
      (node (ref "C27") (pin "2") (pinfunction "2_2") (pintype "passive"))
      (node (ref "R32") (pin "1") (pinfunction "1_1") (pintype "passive"))
      (node (ref "U9") (pin "7") (pinfunction "VR2_7") (pintype "bidirectional"))
      (node (ref "U9") (pin "8") (pinfunction "EN_8") (pintype "input"))
    )
    (net (code "101") (name "Net-(U14-AVDD)") (class "Default")
      (node (ref "C9") (pin "1") (pinfunction "1_1") (pintype "passive"))
      (node (ref "R1") (pin "2") (pinfunction "2_2") (pintype "passive"))
      (node (ref "U14") (pin "19") (pinfunction "AVDD_19") (pintype "power_in"))
    )
    (net (code "102") (name "Net-(U14-VDDCORE{slash}VCAP)") (class "Default")
      (node (ref "C3") (pin "2") (pinfunction "2_2") (pintype "passive"))
      (node (ref "U14") (pin "10") (pinfunction "VDDCORE/VCAP_10") (pintype "power_in"))
    )
    (net (code "103") (name "Net-(U14-~{MCLR{slash}}RG5)") (class "Default")
      (node (ref "R3") (pin "1") (pinfunction "1_1") (pintype "passive"))
      (node (ref "U14") (pin "7") (pinfunction "~{MCLR/}RG5_7") (pintype "input"))
    )
    (net (code "104") (name "Net-(U15-OUT1)") (class "Default")
      (node (ref "J2") (pin "1") (pinfunction "1_1") (pintype "passive"))
      (node (ref "U15") (pin "7") (pinfunction "OUT1_7") (pintype "output"))
    )
    (net (code "105") (name "Net-(U15-OUT2)") (class "Default")
      (node (ref "J2") (pin "2") (pinfunction "2_2") (pintype "passive"))
      (node (ref "U15") (pin "9") (pinfunction "OUT2_9") (pintype "input"))
    )
    (net (code "106") (name "unconnected-(J12-Pad1)") (class "Default")
      (node (ref "J12") (pin "1") (pinfunction "1_1") (pintype "passive"))
    )
    (net (code "107") (name "unconnected-(J14-Pad1)") (class "Default")
      (node (ref "J14") (pin "1") (pinfunction "1_1") (pintype "passive"))
    )
    (net (code "108") (name "unconnected-(U$1-1-PadP$2)") (class "Default")
      (node (ref "U$1") (pin "P$2") (pinfunction "1_P$2") (pintype "bidirectional"))
    )
    (net (code "109") (name "unconnected-(U$2-1-PadP$2)") (class "Default")
      (node (ref "U$2") (pin "P$2") (pinfunction "1_P$2") (pintype "bidirectional"))
    )
    (net (code "110") (name "unconnected-(U$7-1-PadP$2)") (class "Default")
      (node (ref "U$7") (pin "P$2") (pinfunction "1_P$2") (pintype "bidirectional"))
    )
    (net (code "111") (name "unconnected-(U$8-1-PadP$2)") (class "Default")
      (node (ref "U$8") (pin "P$2") (pinfunction "1_P$2") (pintype "bidirectional"))
    )
    (net (code "112") (name "unconnected-(U3-FAULT-Pad1)") (class "Default")
      (node (ref "U3") (pin "1") (pinfunction "FAULT_1") (pintype "output"))
    )
    (net (code "113") (name "unconnected-(U4-FAULT-Pad1)") (class "Default")
      (node (ref "U4") (pin "1") (pinfunction "FAULT_1") (pintype "output"))
    )
    (net (code "114") (name "unconnected-(U5-FAULT-Pad1)") (class "Default")
      (node (ref "U5") (pin "1") (pinfunction "FAULT_1") (pintype "output"))
    )
    (net (code "115") (name "unconnected-(U14-RE0{slash}~{RD{slash}}P2D-Pad2)") (class "Default")
      (node (ref "U14") (pin "2") (pinfunction "RE0/~{RD/}P2D_2") (pintype "bidirectional"))
    )
    (net (code "116") (name "unconnected-(U14-RE1{slash}~{WR{slash}}P2C-Pad1)") (class "Default")
      (node (ref "U14") (pin "1") (pinfunction "RE1/~{WR/}P2C_1") (pintype "bidirectional"))
    )
    (net (code "117") (name "unconnected-(U14-RG0{slash}ECCP3{slash}P3A-Pad3)") (class "Default")
      (node (ref "U14") (pin "3") (pinfunction "RG0/ECCP3/P3A_3") (pintype "bidirectional"))
    )
    (net (code "118") (name "unconnected-(U15-FAULT-Pad1)") (class "Default")
      (node (ref "U15") (pin "1") (pinfunction "FAULT_1") (pintype "output"))
    )
  )
)
